# u2f.net
KiCad netlist of a schematic drawn in Altium Designer
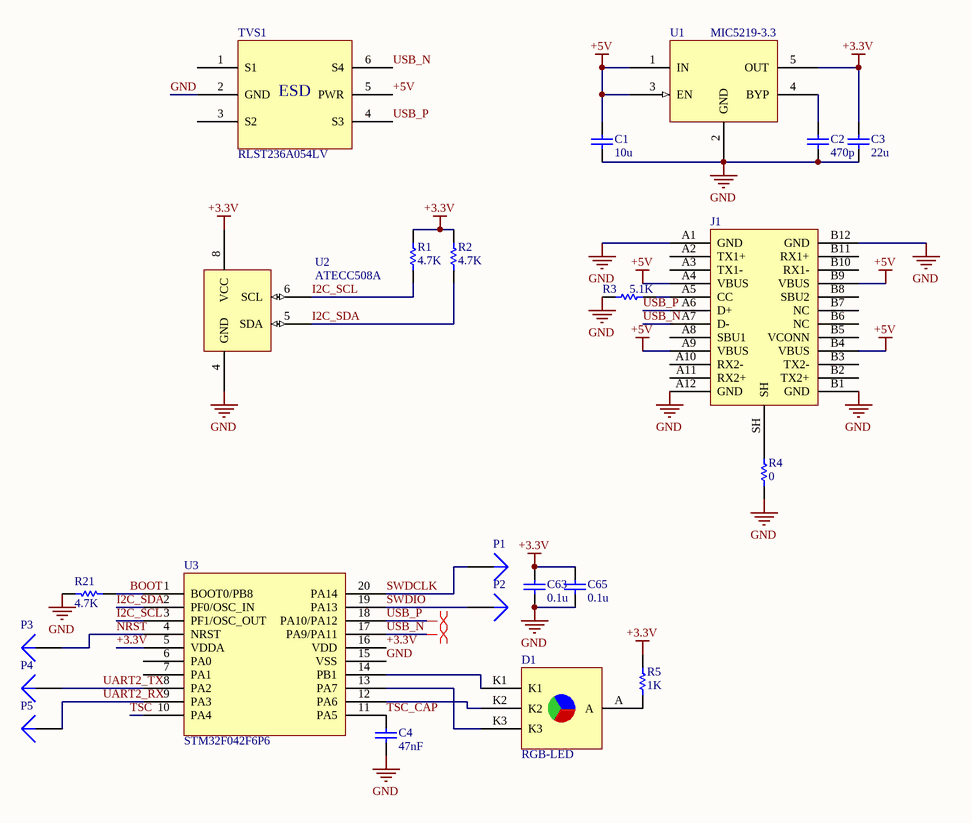
[diagram p0: u2f.SchDoc]

(export (version "E")
  (design (tool "Eeschema 10.0.6"))
  (components
    (comp (ref "C1")
      (value "10u")
      (footprint "C-1608[0603]")
      (description "Capacitor (Semiconductor SIM Model)")
      (fields (field (name "Comment") "Cap Semi") (field (name "PUBLISHER") "Altium Limited"))
      (libsource (lib "Miscellaneous Devices") (part "Cap Semi"))
    )
    (comp (ref "C2")
      (value "470p")
      (footprint "C-1608[0603]")
      (description "Capacitor (Semiconductor SIM Model)")
      (fields (field (name "Comment") "Cap Semi") (field (name "PUBLISHER") "Altium Limited"))
      (libsource (lib "Miscellaneous Devices") (part "Cap Semi"))
    )
    (comp (ref "C3")
      (value "22u")
      (footprint "C-1608[0603]")
      (description "Capacitor (Semiconductor SIM Model)")
      (fields (field (name "Comment") "Cap Semi") (field (name "PUBLISHER") "Altium Limited"))
      (libsource (lib "Miscellaneous Devices") (part "Cap Semi"))
    )
    (comp (ref "C4")
      (value "47nF")
      (footprint "C-1608[0603]")
      (description "Capacitor (Semiconductor SIM Model)")
      (fields (field (name "Comment") "Cap Semi") (field (name "PUBLISHER") "Altium Limited"))
      (libsource (lib "Miscellaneous Devices") (part "Cap Semi"))
    )
    (comp (ref "C63")
      (value "0.1u")
      (footprint "C-1608[0603]")
      (description "Capacitor (Semiconductor SIM Model)")
      (fields (field (name "Comment") "Cap Semi") (field (name "PUBLISHER") "Altium Limited"))
      (libsource (lib "Miscellaneous Devices") (part "Cap Semi"))
    )
    (comp (ref "C65")
      (value "0.1u")
      (footprint "C-1608[0603]")
      (description "Capacitor (Semiconductor SIM Model)")
      (fields (field (name "Comment") "Cap Semi") (field (name "PUBLISHER") "Altium Limited"))
      (libsource (lib "Miscellaneous Devices") (part "Cap Semi"))
    )
    (comp (ref "D1")
      (value "RGB-LED")
      (footprint "LED-1615[0603x2]-RGB")
      (libsource (lib "general") (part "RGBLED_CA"))
    )
    (comp (ref "J1")
      (value "USB-TypeC-Male")
      (footprint "USB-TypeC-Male")
      (libsource (lib "general") (part "USB-TypeC-Male"))
    )
    (comp (ref "P1")
      (value "Plug")
      (footprint "TESTPOINT")
      (fields (field (name "PUBLISHER") "Altium Limited"))
      (libsource (lib "Miscellaneous Connectors") (part "Plug"))
    )
    (comp (ref "P2")
      (value "Plug")
      (footprint "TESTPOINT")
      (fields (field (name "PUBLISHER") "Altium Limited"))
      (libsource (lib "Miscellaneous Connectors") (part "Plug"))
    )
    (comp (ref "P3")
      (value "Plug")
      (footprint "TESTPOINT")
      (fields (field (name "PUBLISHER") "Altium Limited"))
      (libsource (lib "Miscellaneous Connectors") (part "Plug"))
    )
    (comp (ref "P4")
      (value "Plug")
      (footprint "TESTPOINT")
      (fields (field (name "PUBLISHER") "Altium Limited"))
      (libsource (lib "Miscellaneous Connectors") (part "Plug"))
    )
    (comp (ref "P5")
      (value "Plug")
      (footprint "TESTPOINT")
      (fields (field (name "PUBLISHER") "Altium Limited"))
      (libsource (lib "Miscellaneous Connectors") (part "Plug"))
    )
    (comp (ref "R1")
      (value "4.7K")
      (footprint "R-1608[0603]")
      (description "Semiconductor Resistor")
      (fields (field (name "Comment") "Res Semi") (field (name "PUBLISHER") "Altium Limited"))
      (libsource (lib "Miscellaneous Devices") (part "Res Semi"))
    )
    (comp (ref "R2")
      (value "4.7K")
      (footprint "R-1608[0603]")
      (description "Semiconductor Resistor")
      (fields (field (name "Comment") "Res Semi") (field (name "PUBLISHER") "Altium Limited"))
      (libsource (lib "Miscellaneous Devices") (part "Res Semi"))
    )
    (comp (ref "R3")
      (value "5.1K")
      (footprint "R-1608[0603]")
      (description "Semiconductor Resistor")
      (fields (field (name "Comment") "Res Semi") (field (name "PUBLISHER") "Altium Limited"))
      (libsource (lib "Miscellaneous Devices") (part "Res Semi"))
    )
    (comp (ref "R4")
      (value "0")
      (footprint "R-1608[0603]")
      (description "Semiconductor Resistor")
      (fields (field (name "Comment") "Res Semi") (field (name "PUBLISHER") "Altium Limited"))
      (libsource (lib "Miscellaneous Devices") (part "Res Semi"))
    )
    (comp (ref "R5")
      (value "1K")
      (footprint "R-1608[0603]")
      (description "Semiconductor Resistor")
      (fields (field (name "Comment") "Res Semi") (field (name "PUBLISHER") "Altium Limited"))
      (libsource (lib "Miscellaneous Devices") (part "Res Semi"))
    )
    (comp (ref "R21")
      (value "4.7K")
      (footprint "R-1608[0603]")
      (description "Semiconductor Resistor")
      (fields (field (name "Comment") "Res Semi") (field (name "PUBLISHER") "Altium Limited"))
      (libsource (lib "Miscellaneous Devices") (part "Res Semi"))
    )
    (comp (ref "TVS1")
      (value "RLST236A054LV")
      (footprint "SOT23-6")
      (libsource (lib "general") (part "RLST236A054LV"))
    )
    (comp (ref "U1")
      (value "MIC5219-3.3")
      (footprint "SOT23-5")
      (description "500mA-Peak Output LDO Regulator")
      (libsource (lib "general") (part "MIC5219"))
    )
    (comp (ref "U2") (value "ATECC508A") (footprint "SOP8-3D") (libsource (lib "general") (part "ATECC508A")))
    (comp (ref "U3")
      (value "STM32F042F6P6")
      (footprint "TSOP65P640X120-20N")
      (libsource (lib "general") (part "STM32F042FxP"))
    )
  )
  (nets
    (net (code "1") (name "+3.3V") (class "Default")
      (node (ref "C3") (pin "2") (pinfunction "2_2") (pintype "passive"))
      (node (ref "C63") (pin "2") (pinfunction "2_2") (pintype "passive"))
      (node (ref "C65") (pin "2") (pinfunction "2_2") (pintype "passive"))
      (node (ref "R1") (pin "2") (pinfunction "2_2") (pintype "passive"))
      (node (ref "R2") (pin "2") (pinfunction "2_2") (pintype "passive"))
      (node (ref "R5") (pin "2") (pinfunction "2_2") (pintype "passive"))
      (node (ref "U1") (pin "5") (pinfunction "OUT_5") (pintype "passive"))
      (node (ref "U2") (pin "8") (pinfunction "VCC_8") (pintype "power_in"))
      (node (ref "U3") (pin "16") (pinfunction "VDD_16") (pintype "passive"))
      (node (ref "U3") (pin "5") (pinfunction "VDDA_5") (pintype "passive"))
    )
    (net (code "2") (name "+5V") (class "Default")
      (node (ref "C1") (pin "2") (pinfunction "2_2") (pintype "passive"))
      (node (ref "J1") (pin "A4") (pinfunction "VBUS_A4") (pintype "passive"))
      (node (ref "J1") (pin "A9") (pinfunction "VBUS_A9") (pintype "passive"))
      (node (ref "J1") (pin "B4") (pinfunction "VBUS_B4") (pintype "passive"))
      (node (ref "J1") (pin "B9") (pinfunction "VBUS_B9") (pintype "passive"))
      (node (ref "TVS1") (pin "5") (pinfunction "PWR_5") (pintype "passive"))
      (node (ref "U1") (pin "1") (pinfunction "IN_1") (pintype "power_in"))
      (node (ref "U1") (pin "3") (pinfunction "EN_3") (pintype "input"))
    )
    (net (code "3") (name "/BOOT") (class "Default")
      (node (ref "R21") (pin "1") (pinfunction "1_1") (pintype "passive"))
      (node (ref "U3") (pin "1") (pinfunction "BOOT0/PB8_1") (pintype "passive"))
    )
    (net (code "4") (name "/I2C_SCL") (class "Default")
      (node (ref "R1") (pin "1") (pinfunction "1_1") (pintype "passive"))
      (node (ref "U2") (pin "6") (pinfunction "SCL_6") (pintype "bidirectional"))
      (node (ref "U3") (pin "3") (pinfunction "PF1/OSC_OUT_3") (pintype "passive"))
    )
    (net (code "5") (name "/I2C_SDA") (class "Default")
      (node (ref "R2") (pin "1") (pinfunction "1_1") (pintype "passive"))
      (node (ref "U2") (pin "5") (pinfunction "SDA_5") (pintype "bidirectional"))
      (node (ref "U3") (pin "2") (pinfunction "PF0/OSC_IN_2") (pintype "passive"))
    )
    (net (code "6") (name "/NRST") (class "Default")
      (node (ref "P3") (pin "1") (pinfunction "1_1") (pintype "passive"))
      (node (ref "U3") (pin "4") (pinfunction "NRST_4") (pintype "passive"))
    )
    (net (code "7") (name "/SWDCLK") (class "Default")
      (node (ref "P1") (pin "1") (pinfunction "1_1") (pintype "passive"))
      (node (ref "U3") (pin "20") (pinfunction "PA14_20") (pintype "passive"))
    )
    (net (code "8") (name "/SWDIO") (class "Default")
      (node (ref "P2") (pin "1") (pinfunction "1_1") (pintype "passive"))
      (node (ref "U3") (pin "19") (pinfunction "PA13_19") (pintype "passive"))
    )
    (net (code "9") (name "/TSC") (class "Default")
      (node (ref "U3") (pin "10") (pinfunction "PA4_10") (pintype "passive"))
    )
    (net (code "10") (name "/TSC_CAP") (class "Default")
      (node (ref "C4") (pin "2") (pinfunction "2_2") (pintype "passive"))
      (node (ref "U3") (pin "11") (pinfunction "PA5_11") (pintype "passive"))
    )
    (net (code "11") (name "/UART2_RX") (class "Default")
      (node (ref "P5") (pin "1") (pinfunction "1_1") (pintype "passive"))
      (node (ref "U3") (pin "9") (pinfunction "PA3_9") (pintype "passive"))
    )
    (net (code "12") (name "/UART2_TX") (class "Default")
      (node (ref "P4") (pin "1") (pinfunction "1_1") (pintype "passive"))
      (node (ref "U3") (pin "8") (pinfunction "PA2_8") (pintype "passive"))
    )
    (net (code "13") (name "/USB_N") (class "Default")
      (node (ref "J1") (pin "A7") (pinfunction "D-_A7") (pintype "passive"))
      (node (ref "TVS1") (pin "6") (pinfunction "S4_6") (pintype "passive"))
      (node (ref "U3") (pin "17") (pinfunction "PA9/PA11_17") (pintype "passive"))
    )
    (net (code "14") (name "/USB_P") (class "Default")
      (node (ref "J1") (pin "A6") (pinfunction "D+_A6") (pintype "passive"))
      (node (ref "TVS1") (pin "4") (pinfunction "S3_4") (pintype "passive"))
      (node (ref "U3") (pin "18") (pinfunction "PA10/PA12_18") (pintype "passive"))
    )
    (net (code "15") (name "GND") (class "Default")
      (node (ref "C1") (pin "1") (pinfunction "1_1") (pintype "passive"))
      (node (ref "C2") (pin "1") (pinfunction "1_1") (pintype "passive"))
      (node (ref "C3") (pin "1") (pinfunction "1_1") (pintype "passive"))
      (node (ref "C4") (pin "1") (pinfunction "1_1") (pintype "passive"))
      (node (ref "C63") (pin "1") (pinfunction "1_1") (pintype "passive"))
      (node (ref "C65") (pin "1") (pinfunction "1_1") (pintype "passive"))
      (node (ref "J1") (pin "A1") (pinfunction "GND_A1") (pintype "passive"))
      (node (ref "J1") (pin "A12") (pinfunction "GND_A12") (pintype "passive"))
      (node (ref "J1") (pin "B1") (pinfunction "GND_B1") (pintype "passive"))
      (node (ref "J1") (pin "B12") (pinfunction "GND_B12") (pintype "passive"))
      (node (ref "R21") (pin "2") (pinfunction "2_2") (pintype "passive"))
      (node (ref "R3") (pin "2") (pinfunction "2_2") (pintype "passive"))
      (node (ref "R4") (pin "1") (pinfunction "1_1") (pintype "passive"))
      (node (ref "TVS1") (pin "2") (pinfunction "GND_2") (pintype "passive"))
      (node (ref "U1") (pin "2") (pinfunction "GND_2") (pintype "passive"))
      (node (ref "U2") (pin "4") (pinfunction "GND_4") (pintype "power_in"))
      (node (ref "U3") (pin "15") (pinfunction "VSS_15") (pintype "passive"))
    )
    (net (code "16") (name "Net-(D1-PadA)") (class "Default")
      (node (ref "D1") (pin "A") (pinfunction "A_A") (pintype "passive"))
      (node (ref "R5") (pin "1") (pinfunction "1_1") (pintype "passive"))
    )
    (net (code "17") (name "Net-(J1-CC)") (class "Default")
      (node (ref "J1") (pin "A5") (pinfunction "CC_A5") (pintype "passive"))
      (node (ref "R3") (pin "1") (pinfunction "1_1") (pintype "passive"))
    )
    (net (code "18") (name "Net-(J1-PadSH)") (class "Default")
      (node (ref "J1") (pin "SH") (pinfunction "SH_SH") (pintype "passive"))
      (node (ref "R4") (pin "2") (pinfunction "2_2") (pintype "passive"))
    )
    (net (code "19") (name "Net-(U1-BYP)") (class "Default")
      (node (ref "C2") (pin "2") (pinfunction "2_2") (pintype "passive"))
      (node (ref "U1") (pin "4") (pinfunction "BYP_4") (pintype "passive"))
    )
    (net (code "20") (name "Net-(U3-PA6)") (class "Default")
      (node (ref "D1") (pin "K2") (pinfunction "K2_K2") (pintype "passive"))
      (node (ref "U3") (pin "12") (pinfunction "PA6_12") (pintype "passive"))
    )
    (net (code "21") (name "Net-(U3-PA7)") (class "Default")
      (node (ref "D1") (pin "K3") (pinfunction "K3_K3") (pintype "power_in"))
      (node (ref "U3") (pin "13") (pinfunction "PA7_13") (pintype "passive"))
    )
    (net (code "22") (name "Net-(U3-PB1)") (class "Default")
      (node (ref "D1") (pin "K1") (pinfunction "K1_K1") (pintype "passive"))
      (node (ref "U3") (pin "14") (pinfunction "PB1_14") (pintype "passive"))
    )
    (net (code "23") (name "unconnected-(J1-NC-PadB6)") (class "Default")
      (node (ref "J1") (pin "B6") (pinfunction "NC_B6") (pintype "passive"))
    )
    (net (code "24") (name "unconnected-(J1-NC-PadB7)") (class "Default")
      (node (ref "J1") (pin "B7") (pinfunction "NC_B7") (pintype "passive"))
    )
    (net (code "25") (name "unconnected-(J1-RX1+-PadB11)") (class "Default")
      (node (ref "J1") (pin "B11") (pinfunction "RX1+_B11") (pintype "passive"))
    )
    (net (code "26") (name "unconnected-(J1-RX1--PadB10)") (class "Default")
      (node (ref "J1") (pin "B10") (pinfunction "RX1-_B10") (pintype "passive"))
    )
    (net (code "27") (name "unconnected-(J1-RX2+-PadA11)") (class "Default")
      (node (ref "J1") (pin "A11") (pinfunction "RX2+_A11") (pintype "passive"))
    )
    (net (code "28") (name "unconnected-(J1-RX2--PadA10)") (class "Default")
      (node (ref "J1") (pin "A10") (pinfunction "RX2-_A10") (pintype "passive"))
    )
    (net (code "29") (name "unconnected-(J1-SBU1-PadA8)") (class "Default")
      (node (ref "J1") (pin "A8") (pinfunction "SBU1_A8") (pintype "passive"))
    )
    (net (code "30") (name "unconnected-(J1-SBU2-PadB8)") (class "Default")
      (node (ref "J1") (pin "B8") (pinfunction "SBU2_B8") (pintype "passive"))
    )
    (net (code "31") (name "unconnected-(J1-TX1+-PadA2)") (class "Default")
      (node (ref "J1") (pin "A2") (pinfunction "TX1+_A2") (pintype "passive"))
    )
    (net (code "32") (name "unconnected-(J1-TX1--PadA3)") (class "Default")
      (node (ref "J1") (pin "A3") (pinfunction "TX1-_A3") (pintype "passive"))
    )
    (net (code "33") (name "unconnected-(J1-TX2+-PadB2)") (class "Default")
      (node (ref "J1") (pin "B2") (pinfunction "TX2+_B2") (pintype "passive"))
    )
    (net (code "34") (name "unconnected-(J1-TX2--PadB3)") (class "Default")
      (node (ref "J1") (pin "B3") (pinfunction "TX2-_B3") (pintype "passive"))
    )
    (net (code "35") (name "unconnected-(J1-VCONN-PadB5)") (class "Default")
      (node (ref "J1") (pin "B5") (pinfunction "VCONN_B5") (pintype "passive"))
    )
    (net (code "36") (name "unconnected-(TVS1-S1-Pad1)") (class "Default")
      (node (ref "TVS1") (pin "1") (pinfunction "S1_1") (pintype "passive"))
    )
    (net (code "37") (name "unconnected-(TVS1-S2-Pad3)") (class "Default")
      (node (ref "TVS1") (pin "3") (pinfunction "S2_3") (pintype "passive"))
    )
    (net (code "38") (name "unconnected-(U3-PA0-Pad6)") (class "Default")
      (node (ref "U3") (pin "6") (pinfunction "PA0_6") (pintype "passive"))
    )
    (net (code "39") (name "unconnected-(U3-PA1-Pad7)") (class "Default")
      (node (ref "U3") (pin "7") (pinfunction "PA1_7") (pintype "passive"))
    )
  )
)
